# 3_cpu_control.net
KiCad netlist of a schematic drawn in EAGLE
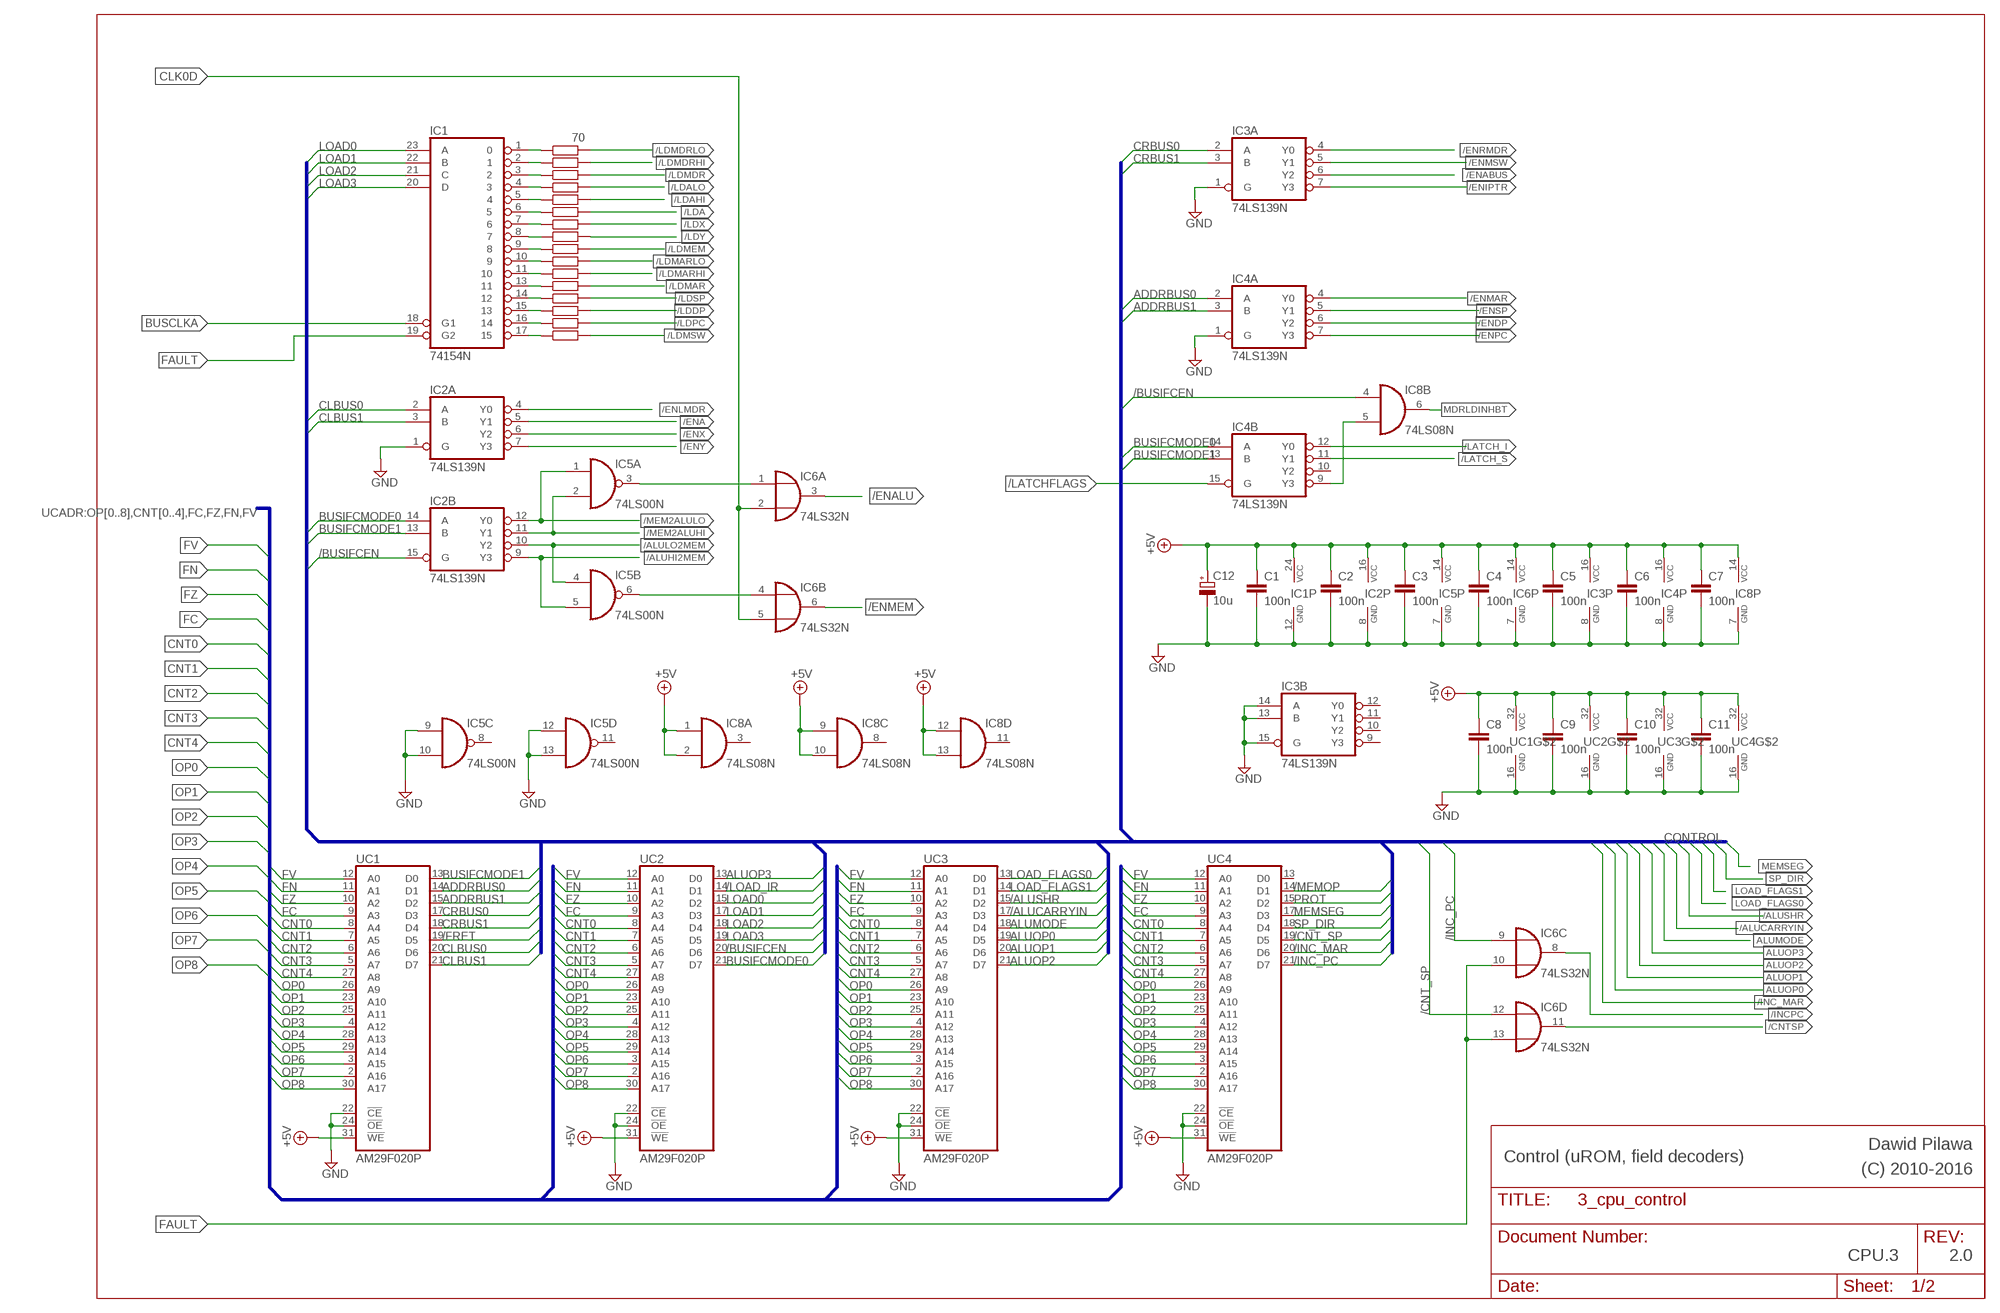
[diagram p0: schematic, sheet 1]
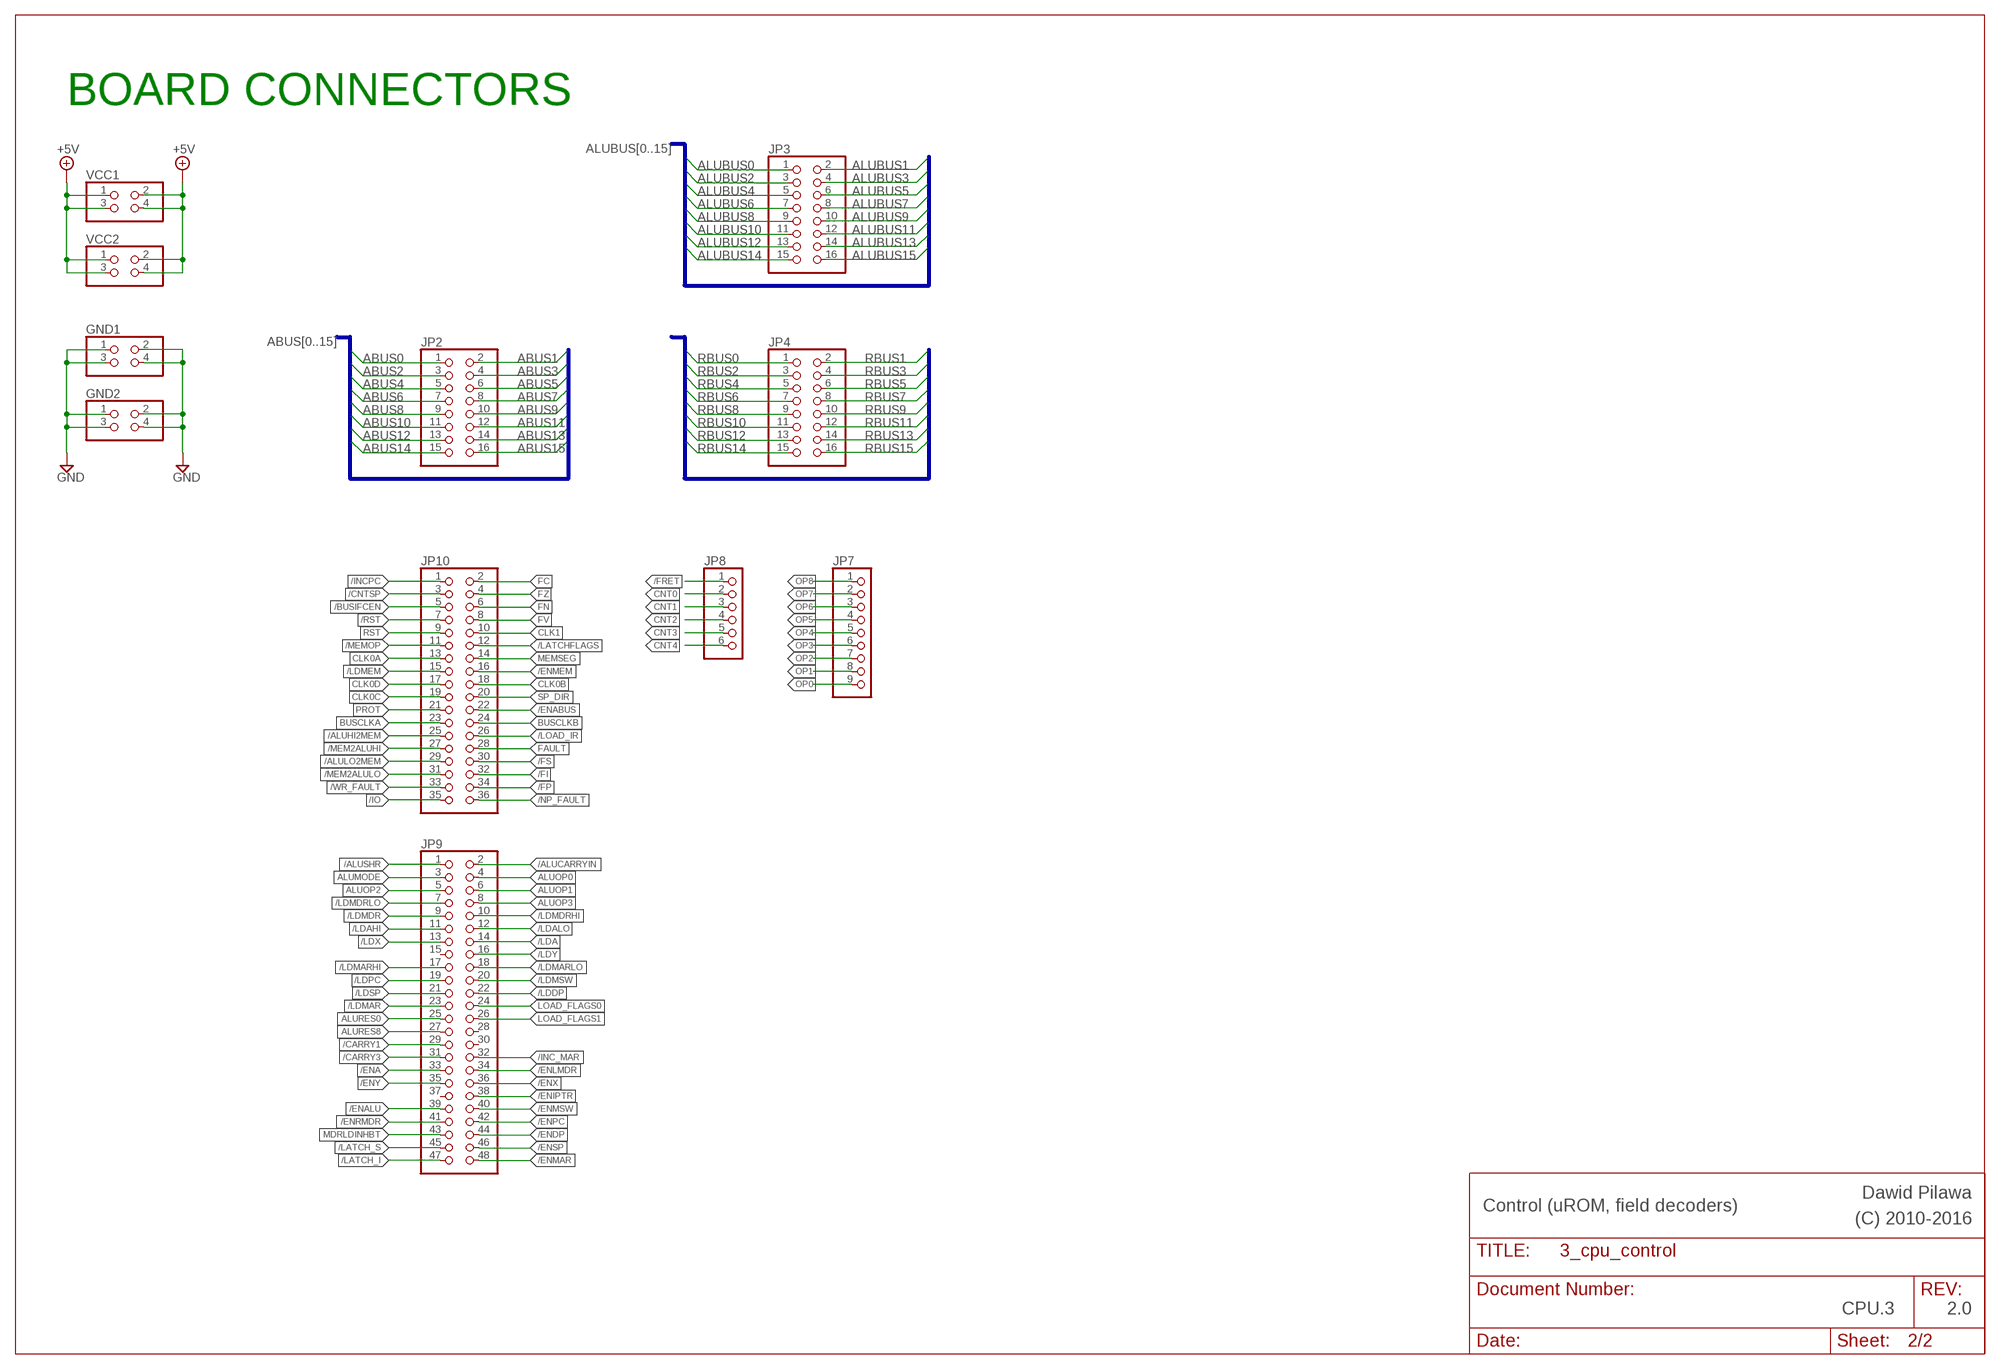
[diagram p1: schematic, sheet 2]

(export (version "E")
  (design (tool "Eeschema 10.0.6"))
  (components
    (comp (ref "C1")
      (value "100n")
      (footprint "eagle-import:C050-024X044")
      (libsource (lib "eagle-import") (part "C-EU050-024X044"))
    )
    (comp (ref "C2")
      (value "100n")
      (footprint "eagle-import:C050-024X044")
      (libsource (lib "eagle-import") (part "C-EU050-024X044"))
    )
    (comp (ref "C3")
      (value "100n")
      (footprint "eagle-import:C050-024X044")
      (libsource (lib "eagle-import") (part "C-EU050-024X044"))
    )
    (comp (ref "C4")
      (value "100n")
      (footprint "eagle-import:C050-024X044")
      (libsource (lib "eagle-import") (part "C-EU050-024X044"))
    )
    (comp (ref "C5")
      (value "100n")
      (footprint "eagle-import:C050-024X044")
      (libsource (lib "eagle-import") (part "C-EU050-024X044"))
    )
    (comp (ref "C6")
      (value "100n")
      (footprint "eagle-import:C050-024X044")
      (libsource (lib "eagle-import") (part "C-EU050-024X044"))
    )
    (comp (ref "C7")
      (value "100n")
      (footprint "eagle-import:C050-024X044")
      (libsource (lib "eagle-import") (part "C-EU050-024X044"))
    )
    (comp (ref "C8")
      (value "100n")
      (footprint "eagle-import:C050-024X044")
      (libsource (lib "eagle-import") (part "C-EU050-024X044"))
    )
    (comp (ref "C9")
      (value "100n")
      (footprint "eagle-import:C050-024X044")
      (libsource (lib "eagle-import") (part "C-EU050-024X044"))
    )
    (comp (ref "C10")
      (value "100n")
      (footprint "eagle-import:C050-024X044")
      (libsource (lib "eagle-import") (part "C-EU050-024X044"))
    )
    (comp (ref "C11")
      (value "100n")
      (footprint "eagle-import:C050-024X044")
      (libsource (lib "eagle-import") (part "C-EU050-024X044"))
    )
    (comp (ref "C12")
      (value "10u")
      (footprint "eagle-import:E5-6")
      (libsource (lib "eagle-import") (part "CPOL-EUE5-6"))
    )
    (comp (ref "IC1")
      (value "74154N")
      (footprint "eagle-import:DIL24-6")
      (libsource (lib "eagle-import") (part "74154N"))
    )
    (comp (ref "IC2")
      (value "74LS139N")
      (footprint "eagle-import:DIL16")
      (libsource (lib "eagle-import") (part "74139NLS"))
    )
    (comp (ref "IC3")
      (value "74LS139N")
      (footprint "eagle-import:DIL16")
      (libsource (lib "eagle-import") (part "74139NLS"))
    )
    (comp (ref "IC4")
      (value "74LS139N")
      (footprint "eagle-import:DIL16")
      (libsource (lib "eagle-import") (part "74139NLS"))
    )
    (comp (ref "IC5")
      (value "74LS00N")
      (footprint "eagle-import:DIL14")
      (libsource (lib "eagle-import") (part "7400NLS"))
    )
    (comp (ref "IC6")
      (value "74LS32N")
      (footprint "eagle-import:DIL14")
      (libsource (lib "eagle-import") (part "7432NLS"))
    )
    (comp (ref "IC8")
      (value "74LS08N")
      (footprint "eagle-import:DIL14")
      (libsource (lib "eagle-import") (part "7408NLS"))
    )
    (comp (ref "R1")
      (value "70")
      (footprint "eagle-import:0204_7")
      (libsource (lib "eagle-import") (part "R-EU_0204/7"))
    )
    (comp (ref "R2")
      (value "R-EU_0204/7")
      (footprint "eagle-import:0204_7")
      (libsource (lib "eagle-import") (part "R-EU_0204/7"))
    )
    (comp (ref "R3")
      (value "R-EU_0204/7")
      (footprint "eagle-import:0204_7")
      (libsource (lib "eagle-import") (part "R-EU_0204/7"))
    )
    (comp (ref "R4")
      (value "R-EU_0204/7")
      (footprint "eagle-import:0204_7")
      (libsource (lib "eagle-import") (part "R-EU_0204/7"))
    )
    (comp (ref "R5")
      (value "R-EU_0204/7")
      (footprint "eagle-import:0204_7")
      (libsource (lib "eagle-import") (part "R-EU_0204/7"))
    )
    (comp (ref "R6")
      (value "R-EU_0204/7")
      (footprint "eagle-import:0204_7")
      (libsource (lib "eagle-import") (part "R-EU_0204/7"))
    )
    (comp (ref "R7")
      (value "R-EU_0204/7")
      (footprint "eagle-import:0204_7")
      (libsource (lib "eagle-import") (part "R-EU_0204/7"))
    )
    (comp (ref "R8")
      (value "R-EU_0204/7")
      (footprint "eagle-import:0204_7")
      (libsource (lib "eagle-import") (part "R-EU_0204/7"))
    )
    (comp (ref "R9")
      (value "R-EU_0204/7")
      (footprint "eagle-import:0204_7")
      (libsource (lib "eagle-import") (part "R-EU_0204/7"))
    )
    (comp (ref "R10")
      (value "R-EU_0204/7")
      (footprint "eagle-import:0204_7")
      (libsource (lib "eagle-import") (part "R-EU_0204/7"))
    )
    (comp (ref "R11")
      (value "R-EU_0204/7")
      (footprint "eagle-import:0204_7")
      (libsource (lib "eagle-import") (part "R-EU_0204/7"))
    )
    (comp (ref "R12")
      (value "R-EU_0204/7")
      (footprint "eagle-import:0204_7")
      (libsource (lib "eagle-import") (part "R-EU_0204/7"))
    )
    (comp (ref "R13")
      (value "R-EU_0204/7")
      (footprint "eagle-import:0204_7")
      (libsource (lib "eagle-import") (part "R-EU_0204/7"))
    )
    (comp (ref "R14")
      (value "R-EU_0204/7")
      (footprint "eagle-import:0204_7")
      (libsource (lib "eagle-import") (part "R-EU_0204/7"))
    )
    (comp (ref "R15")
      (value "R-EU_0204/7")
      (footprint "eagle-import:0204_7")
      (libsource (lib "eagle-import") (part "R-EU_0204/7"))
    )
    (comp (ref "R16")
      (value "R-EU_0204/7")
      (footprint "eagle-import:0204_7")
      (libsource (lib "eagle-import") (part "R-EU_0204/7"))
    )
    (comp (ref "UC1")
      (value "AM29F020P")
      (footprint "eagle-import:DIL32-6")
      (libsource (lib "eagle-import") (part "AM29F020P"))
    )
    (comp (ref "UC2")
      (value "AM29F020P")
      (footprint "eagle-import:DIL32-6")
      (libsource (lib "eagle-import") (part "AM29F020P"))
    )
    (comp (ref "UC3")
      (value "AM29F020P")
      (footprint "eagle-import:DIL32-6")
      (libsource (lib "eagle-import") (part "AM29F020P"))
    )
    (comp (ref "UC4")
      (value "AM29F020P")
      (footprint "eagle-import:DIL32-6")
      (libsource (lib "eagle-import") (part "AM29F020P"))
    )
    (comp (ref "GND1")
      (value "PINHD-2X2")
      (footprint "eagle-import:2X02")
      (libsource (lib "eagle-import") (part "PINHD-2X2"))
    )
    (comp (ref "GND2")
      (value "PINHD-2X2")
      (footprint "eagle-import:2X02")
      (libsource (lib "eagle-import") (part "PINHD-2X2"))
    )
    (comp (ref "JP2")
      (value "PINHD-2X8")
      (footprint "eagle-import:2X08")
      (libsource (lib "eagle-import") (part "PINHD-2X8"))
    )
    (comp (ref "JP3")
      (value "PINHD-2X8")
      (footprint "eagle-import:2X08")
      (libsource (lib "eagle-import") (part "PINHD-2X8"))
    )
    (comp (ref "JP4")
      (value "PINHD-2X8")
      (footprint "eagle-import:2X08")
      (libsource (lib "eagle-import") (part "PINHD-2X8"))
    )
    (comp (ref "JP7")
      (value "PINHD-1X9")
      (footprint "eagle-import:1X09")
      (libsource (lib "eagle-import") (part "PINHD-1X9"))
    )
    (comp (ref "JP8")
      (value "PINHD-1X6")
      (footprint "eagle-import:1X06")
      (libsource (lib "eagle-import") (part "PINHD-1X6"))
    )
    (comp (ref "JP9")
      (value "PINHD-2X24")
      (footprint "eagle-import:2X24")
      (libsource (lib "eagle-import") (part "PINHD-2X24"))
    )
    (comp (ref "JP10")
      (value "PINHD-2X18")
      (footprint "eagle-import:2X18")
      (libsource (lib "eagle-import") (part "PINHD-2X18"))
    )
    (comp (ref "VCC1")
      (value "PINHD-2X2")
      (footprint "eagle-import:2X02")
      (libsource (lib "eagle-import") (part "PINHD-2X2"))
    )
    (comp (ref "VCC2")
      (value "PINHD-2X2")
      (footprint "eagle-import:2X02")
      (libsource (lib "eagle-import") (part "PINHD-2X2"))
    )
  )
  (nets
    (net (code "1") (name "+5V") (class "Default")
      (node (ref "C1") (pin "1") (pinfunction "1_1") (pintype "passive"))
      (node (ref "C10") (pin "1") (pinfunction "1_1") (pintype "passive"))
      (node (ref "C11") (pin "1") (pinfunction "1_1") (pintype "passive"))
      (node (ref "C12") (pin "+") (pinfunction "+_+") (pintype "passive"))
      (node (ref "C2") (pin "1") (pinfunction "1_1") (pintype "passive"))
      (node (ref "C3") (pin "1") (pinfunction "1_1") (pintype "passive"))
      (node (ref "C4") (pin "1") (pinfunction "1_1") (pintype "passive"))
      (node (ref "C5") (pin "1") (pinfunction "1_1") (pintype "passive"))
      (node (ref "C6") (pin "1") (pinfunction "1_1") (pintype "passive"))
      (node (ref "C7") (pin "1") (pinfunction "1_1") (pintype "passive"))
      (node (ref "C8") (pin "1") (pinfunction "1_1") (pintype "passive"))
      (node (ref "C9") (pin "1") (pinfunction "1_1") (pintype "passive"))
      (node (ref "IC1") (pin "24") (pinfunction "VCC_24") (pintype "power_in"))
      (node (ref "IC2") (pin "16") (pinfunction "VCC_16") (pintype "power_in"))
      (node (ref "IC3") (pin "16") (pinfunction "VCC_16") (pintype "power_in"))
      (node (ref "IC4") (pin "16") (pinfunction "VCC_16") (pintype "power_in"))
      (node (ref "IC5") (pin "14") (pinfunction "VCC_14") (pintype "power_in"))
      (node (ref "IC6") (pin "14") (pinfunction "VCC_14") (pintype "power_in"))
      (node (ref "IC8") (pin "1") (pinfunction "I0_1") (pintype "input"))
      (node (ref "IC8") (pin "10") (pinfunction "I1_10") (pintype "input"))
      (node (ref "IC8") (pin "12") (pinfunction "I0_12") (pintype "input"))
      (node (ref "IC8") (pin "13") (pinfunction "I1_13") (pintype "input"))
      (node (ref "IC8") (pin "14") (pinfunction "VCC_14") (pintype "power_in"))
      (node (ref "IC8") (pin "2") (pinfunction "I1_2") (pintype "input"))
      (node (ref "IC8") (pin "9") (pinfunction "I0_9") (pintype "input"))
      (node (ref "UC1") (pin "31") (pinfunction "~{WE}_31") (pintype "input"))
      (node (ref "UC1") (pin "32") (pinfunction "AVCC_32") (pintype "power_in"))
      (node (ref "UC2") (pin "31") (pinfunction "~{WE}_31") (pintype "input"))
      (node (ref "UC2") (pin "32") (pinfunction "AVCC_32") (pintype "power_in"))
      (node (ref "UC3") (pin "31") (pinfunction "~{WE}_31") (pintype "input"))
      (node (ref "UC3") (pin "32") (pinfunction "AVCC_32") (pintype "power_in"))
      (node (ref "UC4") (pin "31") (pinfunction "~{WE}_31") (pintype "input"))
      (node (ref "UC4") (pin "32") (pinfunction "AVCC_32") (pintype "power_in"))
      (node (ref "VCC1") (pin "1") (pinfunction "1_1") (pintype "passive"))
      (node (ref "VCC1") (pin "2") (pinfunction "2_2") (pintype "passive"))
      (node (ref "VCC1") (pin "3") (pinfunction "3_3") (pintype "passive"))
      (node (ref "VCC1") (pin "4") (pinfunction "4_4") (pintype "passive"))
      (node (ref "VCC2") (pin "1") (pinfunction "1_1") (pintype "passive"))
      (node (ref "VCC2") (pin "2") (pinfunction "2_2") (pintype "passive"))
      (node (ref "VCC2") (pin "3") (pinfunction "3_3") (pintype "passive"))
      (node (ref "VCC2") (pin "4") (pinfunction "4_4") (pintype "passive"))
    )
    (net (code "5") (name "ABUS0") (class "Default")
      (node (ref "JP2") (pin "1") (pinfunction "1_1") (pintype "passive"))
    )
    (net (code "6") (name "ABUS1") (class "Default")
      (node (ref "JP2") (pin "2") (pinfunction "2_2") (pintype "passive"))
    )
    (net (code "7") (name "ABUS2") (class "Default")
      (node (ref "JP2") (pin "3") (pinfunction "3_3") (pintype "passive"))
    )
    (net (code "8") (name "ABUS3") (class "Default")
      (node (ref "JP2") (pin "4") (pinfunction "4_4") (pintype "passive"))
    )
    (net (code "9") (name "ABUS4") (class "Default")
      (node (ref "JP2") (pin "5") (pinfunction "5_5") (pintype "passive"))
    )
    (net (code "10") (name "ABUS5") (class "Default")
      (node (ref "JP2") (pin "6") (pinfunction "6_6") (pintype "passive"))
    )
    (net (code "11") (name "ABUS6") (class "Default")
      (node (ref "JP2") (pin "7") (pinfunction "7_7") (pintype "passive"))
    )
    (net (code "12") (name "ABUS7") (class "Default")
      (node (ref "JP2") (pin "8") (pinfunction "8_8") (pintype "passive"))
    )
    (net (code "13") (name "ABUS8") (class "Default")
      (node (ref "JP2") (pin "9") (pinfunction "9_9") (pintype "passive"))
    )
    (net (code "14") (name "ABUS9") (class "Default")
      (node (ref "JP2") (pin "10") (pinfunction "10_10") (pintype "passive"))
    )
    (net (code "15") (name "ABUS10") (class "Default")
      (node (ref "JP2") (pin "11") (pinfunction "11_11") (pintype "passive"))
    )
    (net (code "16") (name "ABUS11") (class "Default")
      (node (ref "JP2") (pin "12") (pinfunction "12_12") (pintype "passive"))
    )
    (net (code "17") (name "ABUS12") (class "Default")
      (node (ref "JP2") (pin "13") (pinfunction "13_13") (pintype "passive"))
    )
    (net (code "18") (name "ABUS13") (class "Default")
      (node (ref "JP2") (pin "14") (pinfunction "14_14") (pintype "passive"))
    )
    (net (code "19") (name "ABUS14") (class "Default")
      (node (ref "JP2") (pin "15") (pinfunction "15_15") (pintype "passive"))
    )
    (net (code "20") (name "ABUS15") (class "Default")
      (node (ref "JP2") (pin "16") (pinfunction "16_16") (pintype "passive"))
    )
    (net (code "21") (name "ADDRBUS0") (class "Default")
      (node (ref "IC4") (pin "2") (pinfunction "A_2") (pintype "input"))
      (node (ref "UC1") (pin "14") (pinfunction "D1_14") (pintype "tri_state"))
    )
    (net (code "22") (name "ADDRBUS1") (class "Default")
      (node (ref "IC4") (pin "3") (pinfunction "B_3") (pintype "input"))
      (node (ref "UC1") (pin "15") (pinfunction "D2_15") (pintype "tri_state"))
    )
    (net (code "23") (name "ALUBUS0") (class "Default")
      (node (ref "JP3") (pin "1") (pinfunction "1_1") (pintype "passive"))
    )
    (net (code "24") (name "ALUBUS1") (class "Default")
      (node (ref "JP3") (pin "2") (pinfunction "2_2") (pintype "passive"))
    )
    (net (code "25") (name "ALUBUS2") (class "Default")
      (node (ref "JP3") (pin "3") (pinfunction "3_3") (pintype "passive"))
    )
    (net (code "26") (name "ALUBUS3") (class "Default")
      (node (ref "JP3") (pin "4") (pinfunction "4_4") (pintype "passive"))
    )
    (net (code "27") (name "ALUBUS4") (class "Default")
      (node (ref "JP3") (pin "5") (pinfunction "5_5") (pintype "passive"))
    )
    (net (code "28") (name "ALUBUS5") (class "Default")
      (node (ref "JP3") (pin "6") (pinfunction "6_6") (pintype "passive"))
    )
    (net (code "29") (name "ALUBUS6") (class "Default")
      (node (ref "JP3") (pin "7") (pinfunction "7_7") (pintype "passive"))
    )
    (net (code "30") (name "ALUBUS7") (class "Default")
      (node (ref "JP3") (pin "8") (pinfunction "8_8") (pintype "passive"))
    )
    (net (code "31") (name "ALUBUS8") (class "Default")
      (node (ref "JP3") (pin "9") (pinfunction "9_9") (pintype "passive"))
    )
    (net (code "32") (name "ALUBUS9") (class "Default")
      (node (ref "JP3") (pin "10") (pinfunction "10_10") (pintype "passive"))
    )
    (net (code "33") (name "ALUBUS10") (class "Default")
      (node (ref "JP3") (pin "11") (pinfunction "11_11") (pintype "passive"))
    )
    (net (code "34") (name "ALUBUS11") (class "Default")
      (node (ref "JP3") (pin "12") (pinfunction "12_12") (pintype "passive"))
    )
    (net (code "35") (name "ALUBUS12") (class "Default")
      (node (ref "JP3") (pin "13") (pinfunction "13_13") (pintype "passive"))
    )
    (net (code "36") (name "ALUBUS13") (class "Default")
      (node (ref "JP3") (pin "14") (pinfunction "14_14") (pintype "passive"))
    )
    (net (code "37") (name "ALUBUS14") (class "Default")
      (node (ref "JP3") (pin "15") (pinfunction "15_15") (pintype "passive"))
    )
    (net (code "38") (name "ALUBUS15") (class "Default")
      (node (ref "JP3") (pin "16") (pinfunction "16_16") (pintype "passive"))
    )
    (net (code "39") (name "ALUMODE") (class "Default")
      (node (ref "JP9") (pin "3") (pinfunction "3_3") (pintype "passive"))
      (node (ref "UC3") (pin "18") (pinfunction "D4_18") (pintype "tri_state"))
    )
    (net (code "40") (name "ALUOP0") (class "Default")
      (node (ref "JP9") (pin "4") (pinfunction "4_4") (pintype "passive"))
      (node (ref "UC3") (pin "19") (pinfunction "D5_19") (pintype "tri_state"))
    )
    (net (code "41") (name "ALUOP1") (class "Default")
      (node (ref "JP9") (pin "6") (pinfunction "6_6") (pintype "passive"))
      (node (ref "UC3") (pin "20") (pinfunction "D6_20") (pintype "tri_state"))
    )
    (net (code "42") (name "ALUOP2") (class "Default")
      (node (ref "JP9") (pin "5") (pinfunction "5_5") (pintype "passive"))
      (node (ref "UC3") (pin "21") (pinfunction "D7_21") (pintype "tri_state"))
    )
    (net (code "43") (name "ALUOP3") (class "Default")
      (node (ref "JP9") (pin "8") (pinfunction "8_8") (pintype "passive"))
      (node (ref "UC2") (pin "13") (pinfunction "D0_13") (pintype "tri_state"))
    )
    (net (code "44") (name "ALURES0") (class "Default")
      (node (ref "JP9") (pin "25") (pinfunction "25_25") (pintype "passive"))
    )
    (net (code "45") (name "ALURES8") (class "Default")
      (node (ref "JP9") (pin "27") (pinfunction "27_27") (pintype "passive"))
    )
    (net (code "46") (name "BUSCLKA") (class "Default")
      (node (ref "IC1") (pin "18") (pinfunction "G1_18") (pintype "input"))
      (node (ref "JP10") (pin "23") (pinfunction "23_23") (pintype "passive"))
    )
    (net (code "47") (name "BUSCLKB") (class "Default")
      (node (ref "JP10") (pin "24") (pinfunction "24_24") (pintype "passive"))
    )
    (net (code "48") (name "BUSIFCMODE0") (class "Default")
      (node (ref "IC2") (pin "14") (pinfunction "A_14") (pintype "input"))
      (node (ref "IC4") (pin "14") (pinfunction "A_14") (pintype "input"))
      (node (ref "UC2") (pin "21") (pinfunction "D7_21") (pintype "tri_state"))
    )
    (net (code "49") (name "BUSIFCMODE1") (class "Default")
      (node (ref "IC2") (pin "13") (pinfunction "B_13") (pintype "input"))
      (node (ref "IC4") (pin "13") (pinfunction "B_13") (pintype "input"))
      (node (ref "UC1") (pin "13") (pinfunction "D0_13") (pintype "tri_state"))
    )
    (net (code "50") (name "CLBUS0") (class "Default")
      (node (ref "IC2") (pin "2") (pinfunction "A_2") (pintype "input"))
      (node (ref "UC1") (pin "20") (pinfunction "D6_20") (pintype "tri_state"))
    )
    (net (code "51") (name "CLBUS1") (class "Default")
      (node (ref "IC2") (pin "3") (pinfunction "B_3") (pintype "input"))
      (node (ref "UC1") (pin "21") (pinfunction "D7_21") (pintype "tri_state"))
    )
    (net (code "52") (name "CLK0A") (class "Default")
      (node (ref "JP10") (pin "13") (pinfunction "13_13") (pintype "passive"))
    )
    (net (code "53") (name "CLK0B") (class "Default")
      (node (ref "JP10") (pin "18") (pinfunction "18_18") (pintype "passive"))
    )
    (net (code "54") (name "CLK0C") (class "Default")
      (node (ref "JP10") (pin "19") (pinfunction "19_19") (pintype "passive"))
    )
    (net (code "55") (name "CLK0D") (class "Default")
      (node (ref "IC6") (pin "2") (pinfunction "I1_2") (pintype "input"))
      (node (ref "IC6") (pin "5") (pinfunction "I1_5") (pintype "input"))
      (node (ref "JP10") (pin "17") (pinfunction "17_17") (pintype "passive"))
    )
    (net (code "56") (name "CLK1") (class "Default")
      (node (ref "JP10") (pin "10") (pinfunction "10_10") (pintype "passive"))
    )
    (net (code "57") (name "CNT0") (class "Default")
      (node (ref "JP8") (pin "2") (pinfunction "2_2") (pintype "passive"))
      (node (ref "UC1") (pin "8") (pinfunction "A4_8") (pintype "input"))
      (node (ref "UC2") (pin "8") (pinfunction "A4_8") (pintype "input"))
      (node (ref "UC3") (pin "8") (pinfunction "A4_8") (pintype "input"))
      (node (ref "UC4") (pin "8") (pinfunction "A4_8") (pintype "input"))
    )
    (net (code "58") (name "CNT1") (class "Default")
      (node (ref "JP8") (pin "3") (pinfunction "3_3") (pintype "passive"))
      (node (ref "UC1") (pin "7") (pinfunction "A5_7") (pintype "input"))
      (node (ref "UC2") (pin "7") (pinfunction "A5_7") (pintype "input"))
      (node (ref "UC3") (pin "7") (pinfunction "A5_7") (pintype "input"))
      (node (ref "UC4") (pin "7") (pinfunction "A5_7") (pintype "input"))
    )
    (net (code "59") (name "CNT2") (class "Default")
      (node (ref "JP8") (pin "4") (pinfunction "4_4") (pintype "passive"))
      (node (ref "UC1") (pin "6") (pinfunction "A6_6") (pintype "input"))
      (node (ref "UC2") (pin "6") (pinfunction "A6_6") (pintype "input"))
      (node (ref "UC3") (pin "6") (pinfunction "A6_6") (pintype "input"))
      (node (ref "UC4") (pin "6") (pinfunction "A6_6") (pintype "input"))
    )
    (net (code "60") (name "CNT3") (class "Default")
      (node (ref "JP8") (pin "5") (pinfunction "5_5") (pintype "passive"))
      (node (ref "UC1") (pin "5") (pinfunction "A7_5") (pintype "input"))
      (node (ref "UC2") (pin "5") (pinfunction "A7_5") (pintype "input"))
      (node (ref "UC3") (pin "5") (pinfunction "A7_5") (pintype "input"))
      (node (ref "UC4") (pin "5") (pinfunction "A7_5") (pintype "input"))
    )
    (net (code "61") (name "CNT4") (class "Default")
      (node (ref "JP8") (pin "6") (pinfunction "6_6") (pintype "passive"))
      (node (ref "UC1") (pin "27") (pinfunction "A8_27") (pintype "input"))
      (node (ref "UC2") (pin "27") (pinfunction "A8_27") (pintype "input"))
      (node (ref "UC3") (pin "27") (pinfunction "A8_27") (pintype "input"))
      (node (ref "UC4") (pin "27") (pinfunction "A8_27") (pintype "input"))
    )
    (net (code "62") (name "CRBUS0") (class "Default")
      (node (ref "IC3") (pin "2") (pinfunction "A_2") (pintype "input"))
      (node (ref "UC1") (pin "17") (pinfunction "D3_17") (pintype "tri_state"))
    )
    (net (code "63") (name "CRBUS1") (class "Default")
      (node (ref "IC3") (pin "3") (pinfunction "B_3") (pintype "input"))
      (node (ref "UC1") (pin "18") (pinfunction "D4_18") (pintype "tri_state"))
    )
    (net (code "64") (name "FAULT") (class "Default")
      (node (ref "IC1") (pin "19") (pinfunction "G2_19") (pintype "input"))
      (node (ref "IC6") (pin "10") (pinfunction "I1_10") (pintype "input"))
      (node (ref "IC6") (pin "13") (pinfunction "I1_13") (pintype "input"))
      (node (ref "JP10") (pin "28") (pinfunction "28_28") (pintype "passive"))
    )
    (net (code "65") (name "FC") (class "Default")
      (node (ref "JP10") (pin "2") (pinfunction "2_2") (pintype "passive"))
      (node (ref "UC1") (pin "9") (pinfunction "A3_9") (pintype "input"))
      (node (ref "UC2") (pin "9") (pinfunction "A3_9") (pintype "input"))
      (node (ref "UC3") (pin "9") (pinfunction "A3_9") (pintype "input"))
      (node (ref "UC4") (pin "9") (pinfunction "A3_9") (pintype "input"))
    )
    (net (code "66") (name "FN") (class "Default")
      (node (ref "JP10") (pin "6") (pinfunction "6_6") (pintype "passive"))
      (node (ref "UC1") (pin "11") (pinfunction "A1_11") (pintype "input"))
      (node (ref "UC2") (pin "11") (pinfunction "A1_11") (pintype "input"))
      (node (ref "UC3") (pin "11") (pinfunction "A1_11") (pintype "input"))
      (node (ref "UC4") (pin "11") (pinfunction "A1_11") (pintype "input"))
    )
    (net (code "67") (name "FV") (class "Default")
      (node (ref "JP10") (pin "8") (pinfunction "8_8") (pintype "passive"))
      (node (ref "UC1") (pin "12") (pinfunction "A0_12") (pintype "input"))
      (node (ref "UC2") (pin "12") (pinfunction "A0_12") (pintype "input"))
      (node (ref "UC3") (pin "12") (pinfunction "A0_12") (pintype "input"))
      (node (ref "UC4") (pin "12") (pinfunction "A0_12") (pintype "input"))
    )
    (net (code "68") (name "FZ") (class "Default")
      (node (ref "JP10") (pin "4") (pinfunction "4_4") (pintype "passive"))
      (node (ref "UC1") (pin "10") (pinfunction "A2_10") (pintype "input"))
      (node (ref "UC2") (pin "10") (pinfunction "A2_10") (pintype "input"))
      (node (ref "UC3") (pin "10") (pinfunction "A2_10") (pintype "input"))
      (node (ref "UC4") (pin "10") (pinfunction "A2_10") (pintype "input"))
    )
    (net (code "69") (name "GND") (class "Default")
      (node (ref "C1") (pin "2") (pinfunction "2_2") (pintype "passive"))
      (node (ref "C10") (pin "2") (pinfunction "2_2") (pintype "passive"))
      (node (ref "C11") (pin "2") (pinfunction "2_2") (pintype "passive"))
      (node (ref "C12") (pin "-") (pinfunction "-_-") (pintype "passive"))
      (node (ref "C2") (pin "2") (pinfunction "2_2") (pintype "passive"))
      (node (ref "C3") (pin "2") (pinfunction "2_2") (pintype "passive"))
      (node (ref "C4") (pin "2") (pinfunction "2_2") (pintype "passive"))
      (node (ref "C5") (pin "2") (pinfunction "2_2") (pintype "passive"))
      (node (ref "C6") (pin "2") (pinfunction "2_2") (pintype "passive"))
      (node (ref "C7") (pin "2") (pinfunction "2_2") (pintype "passive"))
      (node (ref "C8") (pin "2") (pinfunction "2_2") (pintype "passive"))
      (node (ref "C9") (pin "2") (pinfunction "2_2") (pintype "passive"))
      (node (ref "GND1") (pin "1") (pinfunction "1_1") (pintype "passive"))
      (node (ref "GND1") (pin "2") (pinfunction "2_2") (pintype "passive"))
      (node (ref "GND1") (pin "3") (pinfunction "3_3") (pintype "passive"))
      (node (ref "GND1") (pin "4") (pinfunction "4_4") (pintype "passive"))
      (node (ref "GND2") (pin "1") (pinfunction "1_1") (pintype "passive"))
      (node (ref "GND2") (pin "2") (pinfunction "2_2") (pintype "passive"))
      (node (ref "GND2") (pin "3") (pinfunction "3_3") (pintype "passive"))
      (node (ref "GND2") (pin "4") (pinfunction "4_4") (pintype "passive"))
      (node (ref "IC1") (pin "12") (pinfunction "GND_12") (pintype "power_in"))
      (node (ref "IC2") (pin "1") (pinfunction "G_1") (pintype "input"))
      (node (ref "IC2") (pin "8") (pinfunction "GND_8") (pintype "power_in"))
      (node (ref "IC3") (pin "1") (pinfunction "G_1") (pintype "input"))
      (node (ref "IC3") (pin "13") (pinfunction "B_13") (pintype "input"))
      (node (ref "IC3") (pin "14") (pinfunction "A_14") (pintype "input"))
      (node (ref "IC3") (pin "15") (pinfunction "G_15") (pintype "input"))
      (node (ref "IC3") (pin "8") (pinfunction "GND_8") (pintype "power_in"))
      (node (ref "IC4") (pin "1") (pinfunction "G_1") (pintype "input"))
      (node (ref "IC4") (pin "8") (pinfunction "GND_8") (pintype "power_in"))
      (node (ref "IC5") (pin "10") (pinfunction "I1_10") (pintype "input"))
      (node (ref "IC5") (pin "12") (pinfunction "I0_12") (pintype "input"))
      (node (ref "IC5") (pin "13") (pinfunction "I1_13") (pintype "input"))
      (node (ref "IC5") (pin "7") (pinfunction "GND_7") (pintype "power_in"))
      (node (ref "IC5") (pin "9") (pinfunction "I0_9") (pintype "input"))
      (node (ref "IC6") (pin "7") (pinfunction "GND_7") (pintype "power_in"))
      (node (ref "IC8") (pin "7") (pinfunction "GND_7") (pintype "power_in"))
      (node (ref "UC1") (pin "16") (pinfunction "AGND_16") (pintype "power_in"))
      (node (ref "UC1") (pin "22") (pinfunction "~{CE}_22") (pintype "input"))
      (node (ref "UC1") (pin "24") (pinfunction "~{OE}_24") (pintype "input"))
      (node (ref "UC2") (pin "16") (pinfunction "AGND_16") (pintype "power_in"))
      (node (ref "UC2") (pin "22") (pinfunction "~{CE}_22") (pintype "input"))
      (node (ref "UC2") (pin "24") (pinfunction "~{OE}_24") (pintype "input"))
      (node (ref "UC3") (pin "16") (pinfunction "AGND_16") (pintype "power_in"))
      (node (ref "UC3") (pin "22") (pinfunction "~{CE}_22") (pintype "input"))
      (node (ref "UC3") (pin "24") (pinfunction "~{OE}_24") (pintype "input"))
      (node (ref "UC4") (pin "16") (pinfunction "AGND_16") (pintype "power_in"))
      (node (ref "UC4") (pin "22") (pinfunction "~{CE}_22") (pintype "input"))
      (node (ref "UC4") (pin "24") (pinfunction "~{OE}_24") (pintype "input"))
    )
    (net (code "70") (name "LOAD0") (class "Default")
      (node (ref "IC1") (pin "23") (pinfunction "A_23") (pintype "input"))
      (node (ref "UC2") (pin "15") (pinfunction "D2_15") (pintype "tri_state"))
    )
    (net (code "71") (name "LOAD1") (class "Default")
      (node (ref "IC1") (pin "22") (pinfunction "B_22") (pintype "input"))
      (node (ref "UC2") (pin "17") (pinfunction "D3_17") (pintype "tri_state"))
    )
    (net (code "72") (name "LOAD2") (class "Default")
      (node (ref "IC1") (pin "21") (pinfunction "C_21") (pintype "input"))
      (node (ref "UC2") (pin "18") (pinfunction "D4_18") (pintype "tri_state"))
    )
    (net (code "73") (name "LOAD3") (class "Default")
      (node (ref "IC1") (pin "20") (pinfunction "D_20") (pintype "input"))
      (node (ref "UC2") (pin "19") (pinfunction "D5_19") (pintype "tri_state"))
    )
    (net (code "74") (name "LOAD_FLAGS0") (class "Default")
      (node (ref "JP9") (pin "24") (pinfunction "24_24") (pintype "passive"))
      (node (ref "UC3") (pin "13") (pinfunction "D0_13") (pintype "tri_state"))
    )
    (net (code "75") (name "LOAD_FLAGS1") (class "Default")
      (node (ref "JP9") (pin "26") (pinfunction "26_26") (pintype "passive"))
      (node (ref "UC3") (pin "14") (pinfunction "D1_14") (pintype "tri_state"))
    )
    (net (code "76") (name "MDRLDINHBT") (class "Default")
      (node (ref "IC8") (pin "6") (pinfunction "O_6") (pintype "output"))
      (node (ref "JP9") (pin "43") (pinfunction "43_43") (pintype "passive"))
    )
    (net (code "77") (name "MEMSEG") (class "Default")
      (node (ref "JP10") (pin "14") (pinfunction "14_14") (pintype "passive"))
      (node (ref "UC4") (pin "17") (pinfunction "D3_17") (pintype "tri_state"))
    )
    (net (code "78") (name "Net-(IC1A-0)") (class "Default")
      (node (ref "IC1") (pin "1") (pinfunction "0_1") (pintype "output"))
      (node (ref "R1") (pin "1") (pinfunction "1_1") (pintype "passive"))
    )
    (net (code "79") (name "Net-(IC1A-1)") (class "Default")
      (node (ref "IC1") (pin "2") (pinfunction "1_2") (pintype "output"))
      (node (ref "R2") (pin "1") (pinfunction "1_1") (pintype "passive"))
    )
    (net (code "80") (name "Net-(IC1A-2)") (class "Default")
      (node (ref "IC1") (pin "3") (pinfunction "2_3") (pintype "output"))
      (node (ref "R3") (pin "1") (pinfunction "1_1") (pintype "passive"))
    )
    (net (code "81") (name "Net-(IC1A-3)") (class "Default")
      (node (ref "IC1") (pin "4") (pinfunction "3_4") (pintype "output"))
      (node (ref "R4") (pin "1") (pinfunction "1_1") (pintype "passive"))
    )
    (net (code "82") (name "Net-(IC1A-4)") (class "Default")
      (node (ref "IC1") (pin "5") (pinfunction "4_5") (pintype "output"))
      (node (ref "R5") (pin "1") (pinfunction "1_1") (pintype "passive"))
    )
    (net (code "83") (name "Net-(IC1A-5)") (class "Default")
      (node (ref "IC1") (pin "6") (pinfunction "5_6") (pintype "output"))
      (node (ref "R6") (pin "1") (pinfunction "1_1") (pintype "passive"))
    )
    (net (code "84") (name "Net-(IC1A-6)") (class "Default")
      (node (ref "IC1") (pin "7") (pinfunction "6_7") (pintype "output"))
      (node (ref "R7") (pin "1") (pinfunction "1_1") (pintype "passive"))
    )
    (net (code "85") (name "Net-(IC1A-7)") (class "Default")
      (node (ref "IC1") (pin "8") (pinfunction "7_8") (pintype "output"))
      (node (ref "R8") (pin "1") (pinfunction "1_1") (pintype "passive"))
    )
    (net (code "86") (name "Net-(IC1A-8)") (class "Default")
      (node (ref "IC1") (pin "9") (pinfunction "8_9") (pintype "output"))
      (node (ref "R9") (pin "1") (pinfunction "1_1") (pintype "passive"))
    )
    (net (code "87") (name "Net-(IC1A-9)") (class "Default")
      (node (ref "IC1") (pin "10") (pinfunction "9_10") (pintype "output"))
      (node (ref "R10") (pin "1") (pinfunction "1_1") (pintype "passive"))
    )
    (net (code "88") (name "Net-(IC1A-10)") (class "Default")
      (node (ref "IC1") (pin "11") (pinfunction "10_11") (pintype "output"))
      (node (ref "R11") (pin "1") (pinfunction "1_1") (pintype "passive"))
    )
    (net (code "89") (name "Net-(IC1A-11)") (class "Default")
      (node (ref "IC1") (pin "13") (pinfunction "11_13") (pintype "output"))
      (node (ref "R12") (pin "1") (pinfunction "1_1") (pintype "passive"))
    )
    (net (code "90") (name "Net-(IC1A-12)") (class "Default")
      (node (ref "IC1") (pin "14") (pinfunction "12_14") (pintype "output"))
      (node (ref "R13") (pin "1") (pinfunction "1_1") (pintype "passive"))
    )
    (net (code "91") (name "Net-(IC1A-13)") (class "Default")
      (node (ref "IC1") (pin "15") (pinfunction "13_15") (pintype "output"))
      (node (ref "R14") (pin "1") (pinfunction "1_1") (pintype "passive"))
    )
    (net (code "92") (name "Net-(IC1A-14)") (class "Default")
      (node (ref "IC1") (pin "16") (pinfunction "14_16") (pintype "output"))
      (node (ref "R15") (pin "1") (pinfunction "1_1") (pintype "passive"))
    )
    (net (code "93") (name "Net-(IC1A-15)") (class "Default")
      (node (ref "IC1") (pin "17") (pinfunction "15_17") (pintype "output"))
      (node (ref "R16") (pin "1") (pinfunction "1_1") (pintype "passive"))
    )
    (net (code "94") (name "Net-(IC4B-Y3)") (class "Default")
      (node (ref "IC4") (pin "9") (pinfunction "Y3_9") (pintype "output"))
      (node (ref "IC8") (pin "5") (pinfunction "I1_5") (pintype "input"))
    )
    (net (code "95") (name "Net-(IC5A-O)") (class "Default")
      (node (ref "IC5") (pin "3") (pinfunction "O_3") (pintype "output"))
      (node (ref "IC6") (pin "1") (pinfunction "I0_1") (pintype "input"))
    )
    (net (code "96") (name "Net-(IC5B-O)") (class "Default")
      (node (ref "IC5") (pin "6") (pinfunction "O_6") (pintype "output"))
      (node (ref "IC6") (pin "4") (pinfunction "I0_4") (pintype "input"))
    )
    (net (code "97") (name "OP0") (class "Default")
      (node (ref "JP7") (pin "9") (pinfunction "9_9") (pintype "passive"))
      (node (ref "UC1") (pin "26") (pinfunction "A9_26") (pintype "input"))
      (node (ref "UC2") (pin "26") (pinfunction "A9_26") (pintype "input"))
      (node (ref "UC3") (pin "26") (pinfunction "A9_26") (pintype "input"))
      (node (ref "UC4") (pin "26") (pinfunction "A9_26") (pintype "input"))
    )
    (net (code "98") (name "OP1") (class "Default")
      (node (ref "JP7") (pin "8") (pinfunction "8_8") (pintype "passive"))
      (node (ref "UC1") (pin "23") (pinfunction "A10_23") (pintype "input"))
      (node (ref "UC2") (pin "23") (pinfunction "A10_23") (pintype "input"))
      (node (ref "UC3") (pin "23") (pinfunction "A10_23") (pintype "input"))
      (node (ref "UC4") (pin "23") (pinfunction "A10_23") (pintype "input"))
    )
    (net (code "99") (name "OP2") (class "Default")
      (node (ref "JP7") (pin "7") (pinfunction "7_7") (pintype "passive"))
      (node (ref "UC1") (pin "25") (pinfunction "A11_25") (pintype "input"))
      (node (ref "UC2") (pin "25") (pinfunction "A11_25") (pintype "input"))
      (node (ref "UC3") (pin "25") (pinfunction "A11_25") (pintype "input"))
      (node (ref "UC4") (pin "25") (pinfunction "A11_25") (pintype "input"))
    )
    (net (code "100") (name "OP3") (class "Default")
      (node (ref "JP7") (pin "6") (pinfunction "6_6") (pintype "passive"))
      (node (ref "UC1") (pin "4") (pinfunction "A12_4") (pintype "input"))
      (node (ref "UC2") (pin "4") (pinfunction "A12_4") (pintype "input"))
      (node (ref "UC3") (pin "4") (pinfunction "A12_4") (pintype "input"))
      (node (ref "UC4") (pin "4") (pinfunction "A12_4") (pintype "input"))
    )
    (net (code "101") (name "OP4") (class "Default")
      (node (ref "JP7") (pin "5") (pinfunction "5_5") (pintype "passive"))
      (node (ref "UC1") (pin "28") (pinfunction "A13_28") (pintype "input"))
      (node (ref "UC2") (pin "28") (pinfunction "A13_28") (pintype "input"))
      (node (ref "UC3") (pin "28") (pinfunction "A13_28") (pintype "input"))
      (node (ref "UC4") (pin "28") (pinfunction "A13_28") (pintype "input"))
    )
    (net (code "102") (name "OP5") (class "Default")
      (node (ref "JP7") (pin "4") (pinfunction "4_4") (pintype "passive"))
      (node (ref "UC1") (pin "29") (pinfunction "A14_29") (pintype "input"))
      (node (ref "UC2") (pin "29") (pinfunction "A14_29") (pintype "input"))
      (node (ref "UC3") (pin "29") (pinfunction "A14_29") (pintype "input"))
      (node (ref "UC4") (pin "29") (pinfunction "A14_29") (pintype "input"))
    )
    (net (code "103") (name "OP6") (class "Default")
      (node (ref "JP7") (pin "3") (pinfunction "3_3") (pintype "passive"))
      (node (ref "UC1") (pin "3") (pinfunction "A15_3") (pintype "input"))
      (node (ref "UC2") (pin "3") (pinfunction "A15_3") (pintype "input"))
      (node (ref "UC3") (pin "3") (pinfunction "A15_3") (pintype "input"))
      (node (ref "UC4") (pin "3") (pinfunction "A15_3") (pintype "input"))
    )
    (net (code "104") (name "OP7") (class "Default")
      (node (ref "JP7") (pin "2") (pinfunction "2_2") (pintype "passive"))
      (node (ref "UC1") (pin "2") (pinfunction "A16_2") (pintype "input"))
      (node (ref "UC2") (pin "2") (pinfunction "A16_2") (pintype "input"))
      (node (ref "UC3") (pin "2") (pinfunction "A16_2") (pintype "input"))
      (node (ref "UC4") (pin "2") (pinfunction "A16_2") (pintype "input"))
    )
    (net (code "105") (name "OP8") (class "Default")
      (node (ref "JP7") (pin "1") (pinfunction "1_1") (pintype "passive"))
      (node (ref "UC1") (pin "30") (pinfunction "A17_30") (pintype "input"))
      (node (ref "UC2") (pin "30") (pinfunction "A17_30") (pintype "input"))
      (node (ref "UC3") (pin "30") (pinfunction "A17_30") (pintype "input"))
      (node (ref "UC4") (pin "30") (pinfunction "A17_30") (pintype "input"))
    )
    (net (code "106") (name "PROT") (class "Default")
      (node (ref "JP10") (pin "21") (pinfunction "21_21") (pintype "passive"))
      (node (ref "UC4") (pin "15") (pinfunction "D2_15") (pintype "tri_state"))
    )
    (net (code "107") (name "RBUS0") (class "Default")
      (node (ref "JP4") (pin "1") (pinfunction "1_1") (pintype "passive"))
    )
    (net (code "108") (name "RBUS1") (class "Default")
      (node (ref "JP4") (pin "2") (pinfunction "2_2") (pintype "passive"))
    )
    (net (code "109") (name "RBUS2") (class "Default")
      (node (ref "JP4") (pin "3") (pinfunction "3_3") (pintype "passive"))
    )
    (net (code "110") (name "RBUS3") (class "Default")
      (node (ref "JP4") (pin "4") (pinfunction "4_4") (pintype "passive"))
    )
    (net (code "111") (name "RBUS4") (class "Default")
      (node (ref "JP4") (pin "5") (pinfunction "5_5") (pintype "passive"))
    )
    (net (code "112") (name "RBUS5") (class "Default")
      (node (ref "JP4") (pin "6") (pinfunction "6_6") (pintype "passive"))
    )
    (net (code "113") (name "RBUS6") (class "Default")
      (node (ref "JP4") (pin "7") (pinfunction "7_7") (pintype "passive"))
    )
    (net (code "114") (name "RBUS7") (class "Default")
      (node (ref "JP4") (pin "8") (pinfunction "8_8") (pintype "passive"))
    )
    (net (code "115") (name "RBUS8") (class "Default")
      (node (ref "JP4") (pin "9") (pinfunction "9_9") (pintype "passive"))
    )
    (net (code "116") (name "RBUS9") (class "Default")
      (node (ref "JP4") (pin "10") (pinfunction "10_10") (pintype "passive"))
    )
    (net (code "117") (name "RBUS10") (class "Default")
      (node (ref "JP4") (pin "11") (pinfunction "11_11") (pintype "passive"))
    )
    (net (code "118") (name "RBUS11") (class "Default")
      (node (ref "JP4") (pin "12") (pinfunction "12_12") (pintype "passive"))
    )
    (net (code "119") (name "RBUS12") (class "Default")
      (node (ref "JP4") (pin "13") (pinfunction "13_13") (pintype "passive"))
    )
    (net (code "120") (name "RBUS13") (class "Default")
      (node (ref "JP4") (pin "14") (pinfunction "14_14") (pintype "passive"))
    )
    (net (code "121") (name "RBUS14") (class "Default")
      (node (ref "JP4") (pin "15") (pinfunction "15_15") (pintype "passive"))
    )
    (net (code "122") (name "RBUS15") (class "Default")
      (node (ref "JP4") (pin "16") (pinfunction "16_16") (pintype "passive"))
    )
    (net (code "123") (name "RST") (class "Default")
      (node (ref "JP10") (pin "9") (pinfunction "9_9") (pintype "passive"))
    )
    (net (code "124") (name "SP_DIR") (class "Default")
      (node (ref "JP10") (pin "20") (pinfunction "20_20") (pintype "passive"))
      (node (ref "UC4") (pin "18") (pinfunction "D4_18") (pintype "tri_state"))
    )
    (net (code "125") (name "unconnected-(IC3B-Y0-Pad12)") (class "Default")
      (node (ref "IC3") (pin "12") (pinfunction "Y0_12") (pintype "output"))
    )
    (net (code "126") (name "unconnected-(IC3B-Y1-Pad11)") (class "Default")
      (node (ref "IC3") (pin "11") (pinfunction "Y1_11") (pintype "output"))
    )
    (net (code "127") (name "unconnected-(IC3B-Y2-Pad10)") (class "Default")
      (node (ref "IC3") (pin "10") (pinfunction "Y2_10") (pintype "output"))
    )
    (net (code "128") (name "unconnected-(IC3B-Y3-Pad9)") (class "Default")
      (node (ref "IC3") (pin "9") (pinfunction "Y3_9") (pintype "output"))
    )
    (net (code "129") (name "unconnected-(IC4B-Y2-Pad10)") (class "Default")
      (node (ref "IC4") (pin "10") (pinfunction "Y2_10") (pintype "output"))
    )
    (net (code "130") (name "unconnected-(IC5C-O-Pad8)") (class "Default")
      (node (ref "IC5") (pin "8") (pinfunction "O_8") (pintype "output"))
    )
    (net (code "131") (name "unconnected-(IC5D-O-Pad11)") (class "Default")
      (node (ref "IC5") (pin "11") (pinfunction "O_11") (pintype "output"))
    )
    (net (code "132") (name "unconnected-(IC8A-O-Pad3)") (class "Default")
      (node (ref "IC8") (pin "3") (pinfunction "O_3") (pintype "output"))
    )
    (net (code "133") (name "unconnected-(IC8C-O-Pad8)") (class "Default")
      (node (ref "IC8") (pin "8") (pinfunction "O_8") (pintype "output"))
    )
    (net (code "134") (name "unconnected-(IC8D-O-Pad11)") (class "Default")
      (node (ref "IC8") (pin "11") (pinfunction "O_11") (pintype "output"))
    )
    (net (code "135") (name "unconnected-(JP9-Pad15)") (class "Default")
      (node (ref "JP9") (pin "15") (pinfunction "15_15") (pintype "passive"))
    )
    (net (code "136") (name "unconnected-(JP9-Pad28)") (class "Default")
      (node (ref "JP9") (pin "28") (pinfunction "28_28") (pintype "passive"))
    )
    (net (code "137") (name "unconnected-(JP9-Pad30)") (class "Default")
      (node (ref "JP9") (pin "30") (pinfunction "30_30") (pintype "passive"))
    )
    (net (code "138") (name "unconnected-(JP9-Pad37)") (class "Default")
      (node (ref "JP9") (pin "37") (pinfunction "37_37") (pintype "passive"))
    )
    (net (code "139") (name "unconnected-(UC4A-D0-Pad13)") (class "Default")
      (node (ref "UC4") (pin "13") (pinfunction "D0_13") (pintype "tri_state"))
    )
    (net (code "140") (name "{slash}ALUCARRYIN") (class "Default")
      (node (ref "JP9") (pin "2") (pinfunction "2_2") (pintype "passive"))
      (node (ref "UC3") (pin "17") (pinfunction "D3_17") (pintype "tri_state"))
    )
    (net (code "141") (name "{slash}ALUHI2MEM") (class "Default")
      (node (ref "IC2") (pin "9") (pinfunction "Y3_9") (pintype "output"))
      (node (ref "IC5") (pin "5") (pinfunction "I1_5") (pintype "input"))
      (node (ref "JP10") (pin "25") (pinfunction "25_25") (pintype "passive"))
    )
    (net (code "142") (name "{slash}ALULO2MEM") (class "Default")
      (node (ref "IC2") (pin "10") (pinfunction "Y2_10") (pintype "output"))
      (node (ref "IC5") (pin "4") (pinfunction "I0_4") (pintype "input"))
      (node (ref "JP10") (pin "29") (pinfunction "29_29") (pintype "passive"))
    )
    (net (code "143") (name "{slash}ALUSHR") (class "Default")
      (node (ref "JP9") (pin "1") (pinfunction "1_1") (pintype "passive"))
      (node (ref "UC3") (pin "15") (pinfunction "D2_15") (pintype "tri_state"))
    )
    (net (code "144") (name "{slash}BUSIFCEN") (class "Default")
      (node (ref "IC2") (pin "15") (pinfunction "G_15") (pintype "input"))
      (node (ref "IC8") (pin "4") (pinfunction "I0_4") (pintype "input"))
      (node (ref "JP10") (pin "5") (pinfunction "5_5") (pintype "passive"))
      (node (ref "UC2") (pin "20") (pinfunction "D6_20") (pintype "tri_state"))
    )
    (net (code "145") (name "{slash}CARRY1") (class "Default")
      (node (ref "JP9") (pin "29") (pinfunction "29_29") (pintype "passive"))
    )
    (net (code "146") (name "{slash}CARRY3") (class "Default")
      (node (ref "JP9") (pin "31") (pinfunction "31_31") (pintype "passive"))
    )
    (net (code "147") (name "{slash}CNTSP") (class "Default")
      (node (ref "IC6") (pin "11") (pinfunction "O_11") (pintype "output"))
      (node (ref "JP10") (pin "3") (pinfunction "3_3") (pintype "passive"))
    )
    (net (code "148") (name "{slash}CNT_SP") (class "Default")
      (node (ref "IC6") (pin "12") (pinfunction "I0_12") (pintype "input"))
      (node (ref "UC4") (pin "19") (pinfunction "D5_19") (pintype "tri_state"))
    )
    (net (code "149") (name "{slash}ENA") (class "Default")
      (node (ref "IC2") (pin "5") (pinfunction "Y1_5") (pintype "output"))
      (node (ref "JP9") (pin "33") (pinfunction "33_33") (pintype "passive"))
    )
    (net (code "150") (name "{slash}ENABUS") (class "Default")
      (node (ref "IC3") (pin "6") (pinfunction "Y2_6") (pintype "output"))
      (node (ref "JP10") (pin "22") (pinfunction "22_22") (pintype "passive"))
    )
    (net (code "151") (name "{slash}ENALU") (class "Default")
      (node (ref "IC6") (pin "3") (pinfunction "O_3") (pintype "output"))
      (node (ref "JP9") (pin "39") (pinfunction "39_39") (pintype "passive"))
    )
    (net (code "152") (name "{slash}ENDP") (class "Default")
      (node (ref "IC4") (pin "6") (pinfunction "Y2_6") (pintype "output"))
      (node (ref "JP9") (pin "44") (pinfunction "44_44") (pintype "passive"))
    )
    (net (code "153") (name "{slash}ENIPTR") (class "Default")
      (node (ref "IC3") (pin "7") (pinfunction "Y3_7") (pintype "output"))
      (node (ref "JP9") (pin "38") (pinfunction "38_38") (pintype "passive"))
    )
    (net (code "154") (name "{slash}ENLMDR") (class "Default")
      (node (ref "IC2") (pin "4") (pinfunction "Y0_4") (pintype "output"))
      (node (ref "JP9") (pin "34") (pinfunction "34_34") (pintype "passive"))
    )
    (net (code "155") (name "{slash}ENMAR") (class "Default")
      (node (ref "IC4") (pin "4") (pinfunction "Y0_4") (pintype "output"))
      (node (ref "JP9") (pin "48") (pinfunction "48_48") (pintype "passive"))
    )
    (net (code "156") (name "{slash}ENMEM") (class "Default")
      (node (ref "IC6") (pin "6") (pinfunction "O_6") (pintype "output"))
      (node (ref "JP10") (pin "16") (pinfunction "16_16") (pintype "passive"))
    )
    (net (code "157") (name "{slash}ENMSW") (class "Default")
      (node (ref "IC3") (pin "5") (pinfunction "Y1_5") (pintype "output"))
      (node (ref "JP9") (pin "40") (pinfunction "40_40") (pintype "passive"))
    )
    (net (code "158") (name "{slash}ENPC") (class "Default")
      (node (ref "IC4") (pin "7") (pinfunction "Y3_7") (pintype "output"))
      (node (ref "JP9") (pin "42") (pinfunction "42_42") (pintype "passive"))
    )
    (net (code "159") (name "{slash}ENRMDR") (class "Default")
      (node (ref "IC3") (pin "4") (pinfunction "Y0_4") (pintype "output"))
      (node (ref "JP9") (pin "41") (pinfunction "41_41") (pintype "passive"))
    )
    (net (code "160") (name "{slash}ENSP") (class "Default")
      (node (ref "IC4") (pin "5") (pinfunction "Y1_5") (pintype "output"))
      (node (ref "JP9") (pin "46") (pinfunction "46_46") (pintype "passive"))
    )
    (net (code "161") (name "{slash}ENX") (class "Default")
      (node (ref "IC2") (pin "6") (pinfunction "Y2_6") (pintype "output"))
      (node (ref "JP9") (pin "36") (pinfunction "36_36") (pintype "passive"))
    )
    (net (code "162") (name "{slash}ENY") (class "Default")
      (node (ref "IC2") (pin "7") (pinfunction "Y3_7") (pintype "output"))
      (node (ref "JP9") (pin "35") (pinfunction "35_35") (pintype "passive"))
    )
    (net (code "163") (name "{slash}FI") (class "Default")
      (node (ref "JP10") (pin "32") (pinfunction "32_32") (pintype "passive"))
    )
    (net (code "164") (name "{slash}FP") (class "Default")
      (node (ref "JP10") (pin "34") (pinfunction "34_34") (pintype "passive"))
    )
    (net (code "165") (name "{slash}FRET") (class "Default")
      (node (ref "JP8") (pin "1") (pinfunction "1_1") (pintype "passive"))
      (node (ref "UC1") (pin "19") (pinfunction "D5_19") (pintype "tri_state"))
    )
    (net (code "166") (name "{slash}FS") (class "Default")
      (node (ref "JP10") (pin "30") (pinfunction "30_30") (pintype "passive"))
    )
    (net (code "167") (name "{slash}INCPC") (class "Default")
      (node (ref "IC6") (pin "8") (pinfunction "O_8") (pintype "output"))
      (node (ref "JP10") (pin "1") (pinfunction "1_1") (pintype "passive"))
    )
    (net (code "168") (name "{slash}INC_MAR") (class "Default")
      (node (ref "JP9") (pin "32") (pinfunction "32_32") (pintype "passive"))
      (node (ref "UC4") (pin "20") (pinfunction "D6_20") (pintype "tri_state"))
    )
    (net (code "169") (name "{slash}INC_PC") (class "Default")
      (node (ref "IC6") (pin "9") (pinfunction "I0_9") (pintype "input"))
      (node (ref "UC4") (pin "21") (pinfunction "D7_21") (pintype "tri_state"))
    )
    (net (code "170") (name "{slash}IO") (class "Default")
      (node (ref "JP10") (pin "35") (pinfunction "35_35") (pintype "passive"))
    )
    (net (code "171") (name "{slash}LATCHFLAGS") (class "Default")
      (node (ref "IC4") (pin "15") (pinfunction "G_15") (pintype "input"))
      (node (ref "JP10") (pin "12") (pinfunction "12_12") (pintype "passive"))
    )
    (net (code "172") (name "{slash}LATCH_I") (class "Default")
      (node (ref "IC4") (pin "12") (pinfunction "Y0_12") (pintype "output"))
      (node (ref "JP9") (pin "47") (pinfunction "47_47") (pintype "passive"))
    )
    (net (code "173") (name "{slash}LATCH_S") (class "Default")
      (node (ref "IC4") (pin "11") (pinfunction "Y1_11") (pintype "output"))
      (node (ref "JP9") (pin "45") (pinfunction "45_45") (pintype "passive"))
    )
    (net (code "174") (name "{slash}LDA") (class "Default")
      (node (ref "JP9") (pin "14") (pinfunction "14_14") (pintype "passive"))
      (node (ref "R6") (pin "2") (pinfunction "2_2") (pintype "passive"))
    )
    (net (code "175") (name "{slash}LDAHI") (class "Default")
      (node (ref "JP9") (pin "11") (pinfunction "11_11") (pintype "passive"))
      (node (ref "R5") (pin "2") (pinfunction "2_2") (pintype "passive"))
    )
    (net (code "176") (name "{slash}LDALO") (class "Default")
      (node (ref "JP9") (pin "12") (pinfunction "12_12") (pintype "passive"))
      (node (ref "R4") (pin "2") (pinfunction "2_2") (pintype "passive"))
    )
    (net (code "177") (name "{slash}LDDP") (class "Default")
      (node (ref "JP9") (pin "22") (pinfunction "22_22") (pintype "passive"))
      (node (ref "R14") (pin "2") (pinfunction "2_2") (pintype "passive"))
    )
    (net (code "178") (name "{slash}LDMAR") (class "Default")
      (node (ref "JP9") (pin "23") (pinfunction "23_23") (pintype "passive"))
      (node (ref "R12") (pin "2") (pinfunction "2_2") (pintype "passive"))
    )
    (net (code "179") (name "{slash}LDMARHI") (class "Default")
      (node (ref "JP9") (pin "17") (pinfunction "17_17") (pintype "passive"))
      (node (ref "R11") (pin "2") (pinfunction "2_2") (pintype "passive"))
    )
    (net (code "180") (name "{slash}LDMARLO") (class "Default")
      (node (ref "JP9") (pin "18") (pinfunction "18_18") (pintype "passive"))
      (node (ref "R10") (pin "2") (pinfunction "2_2") (pintype "passive"))
    )
    (net (code "181") (name "{slash}LDMDR") (class "Default")
      (node (ref "JP9") (pin "9") (pinfunction "9_9") (pintype "passive"))
      (node (ref "R3") (pin "2") (pinfunction "2_2") (pintype "passive"))
    )
    (net (code "182") (name "{slash}LDMDRHI") (class "Default")
      (node (ref "JP9") (pin "10") (pinfunction "10_10") (pintype "passive"))
      (node (ref "R2") (pin "2") (pinfunction "2_2") (pintype "passive"))
    )
    (net (code "183") (name "{slash}LDMDRLO") (class "Default")
      (node (ref "JP9") (pin "7") (pinfunction "7_7") (pintype "passive"))
      (node (ref "R1") (pin "2") (pinfunction "2_2") (pintype "passive"))
    )
    (net (code "184") (name "{slash}LDMEM") (class "Default")
      (node (ref "JP10") (pin "15") (pinfunction "15_15") (pintype "passive"))
      (node (ref "R9") (pin "2") (pinfunction "2_2") (pintype "passive"))
    )
    (net (code "185") (name "{slash}LDMSW") (class "Default")
      (node (ref "JP9") (pin "20") (pinfunction "20_20") (pintype "passive"))
      (node (ref "R16") (pin "2") (pinfunction "2_2") (pintype "passive"))
    )
    (net (code "186") (name "{slash}LDPC") (class "Default")
      (node (ref "JP9") (pin "19") (pinfunction "19_19") (pintype "passive"))
      (node (ref "R15") (pin "2") (pinfunction "2_2") (pintype "passive"))
    )
    (net (code "187") (name "{slash}LDSP") (class "Default")
      (node (ref "JP9") (pin "21") (pinfunction "21_21") (pintype "passive"))
      (node (ref "R13") (pin "2") (pinfunction "2_2") (pintype "passive"))
    )
    (net (code "188") (name "{slash}LDX") (class "Default")
      (node (ref "JP9") (pin "13") (pinfunction "13_13") (pintype "passive"))
      (node (ref "R7") (pin "2") (pinfunction "2_2") (pintype "passive"))
    )
    (net (code "189") (name "{slash}LDY") (class "Default")
      (node (ref "JP9") (pin "16") (pinfunction "16_16") (pintype "passive"))
      (node (ref "R8") (pin "2") (pinfunction "2_2") (pintype "passive"))
    )
    (net (code "190") (name "{slash}LOAD_IR") (class "Default")
      (node (ref "JP10") (pin "26") (pinfunction "26_26") (pintype "passive"))
      (node (ref "UC2") (pin "14") (pinfunction "D1_14") (pintype "tri_state"))
    )
    (net (code "191") (name "{slash}MEM2ALUHI") (class "Default")
      (node (ref "IC2") (pin "11") (pinfunction "Y1_11") (pintype "output"))
      (node (ref "IC5") (pin "2") (pinfunction "I1_2") (pintype "input"))
      (node (ref "JP10") (pin "27") (pinfunction "27_27") (pintype "passive"))
    )
    (net (code "192") (name "{slash}MEM2ALULO") (class "Default")
      (node (ref "IC2") (pin "12") (pinfunction "Y0_12") (pintype "output"))
      (node (ref "IC5") (pin "1") (pinfunction "I0_1") (pintype "input"))
      (node (ref "JP10") (pin "31") (pinfunction "31_31") (pintype "passive"))
    )
    (net (code "193") (name "{slash}MEMOP") (class "Default")
      (node (ref "JP10") (pin "11") (pinfunction "11_11") (pintype "passive"))
      (node (ref "UC4") (pin "14") (pinfunction "D1_14") (pintype "tri_state"))
    )
    (net (code "194") (name "{slash}NP_FAULT") (class "Default")
      (node (ref "JP10") (pin "36") (pinfunction "36_36") (pintype "passive"))
    )
    (net (code "195") (name "{slash}RST") (class "Default")
      (node (ref "JP10") (pin "7") (pinfunction "7_7") (pintype "passive"))
    )
    (net (code "196") (name "{slash}WR_FAULT") (class "Default")
      (node (ref "JP10") (pin "33") (pinfunction "33_33") (pintype "passive"))
    )
  )
)
